# VTTX.net
KiCad netlist of a schematic drawn in Altium Designer
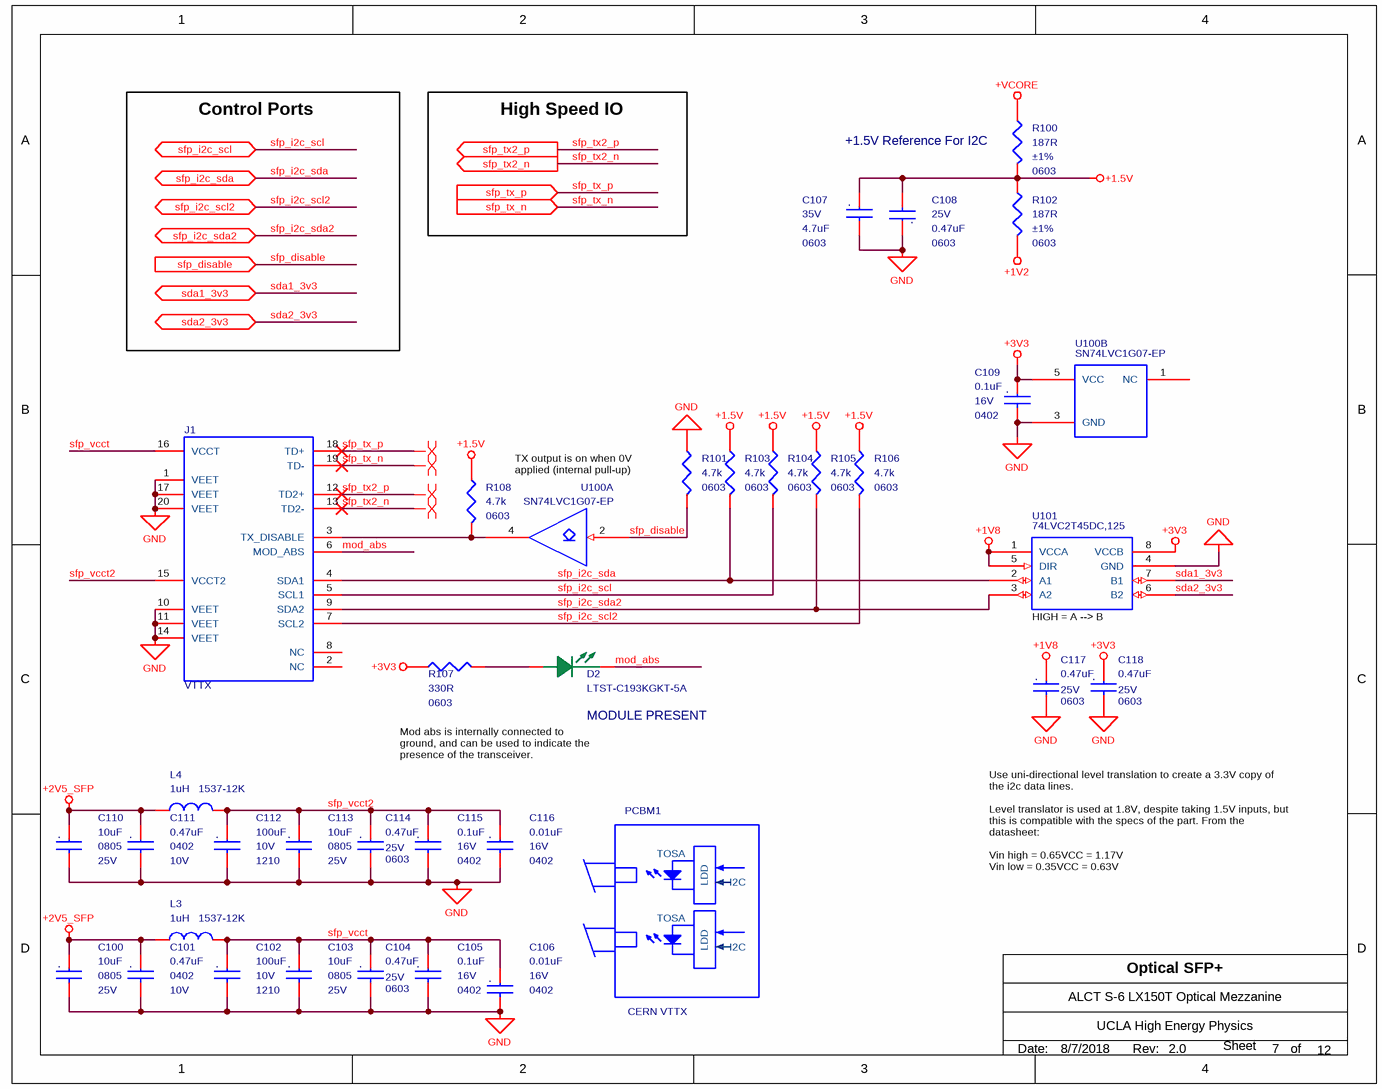
[diagram p0: VTTX.SchDoc]

(export (version "E")
  (design (tool "Eeschema 10.0.6"))
  (components
    (comp (ref "C100")
      (value "10uF")
      (footprint "MC_S6/SM/C_0805_IPC")
      (description "CAP CER 10UF 25V X5R 0805")
      (fields
        (field (name "MANUFACTURER") "Murata Electronics North America")
        (field (name "MANUFACTURER PART NUMBER") "GRM21BR61E106KA73L")
        (field (name "VOLTAGE - RATED") "25V")
        (field (name "PACKAGE") "0805")
      )
      (libsource (lib "ALCT_MEZ_SPARTAN6_Library") (part "GRM21BR61E106KA73L"))
    )
    (comp (ref "C101")
      (value "0.47uF")
      (footprint "MC_S6/SM/C_0402_IPC")
      (description "CAP CER 0.47UF 10V X5R 0402")
      (fields
        (field (name "MANUFACTURER") "Murata Electronics North America")
        (field (name "MANUFACTURER PART NUMBER") "GRM155R61A474KE15J")
        (field (name "VOLTAGE - RATED") "10V")
        (field (name "PACKAGE") "0402")
      )
      (libsource (lib "ALCT_MEZ_SPARTAN6_Library") (part "GRM155R61A474KE15J"))
    )
    (comp (ref "C102")
      (value "100uF")
      (footprint "MC_S6/SM/C_1210_IPC")
      (description "CAP CER 100UF 10V X5R 1210")
      (fields
        (field (name "MANUFACTURER") "Taiyo Yuden")
        (field (name "MANUFACTURER PART NUMBER") "LMK325BJ107MM-T")
        (field (name "VOLTAGE - RATED") "10V")
        (field (name "PACKAGE") "1210")
      )
      (libsource (lib "ALCT_MEZ_SPARTAN6_Library") (part "LMK325BJ107MM-T"))
    )
    (comp (ref "C103")
      (value "10uF")
      (footprint "MC_S6/SM/C_0805_IPC")
      (description "CAP CER 10UF 25V X5R 0805")
      (fields
        (field (name "MANUFACTURER") "Murata Electronics North America")
        (field (name "MANUFACTURER PART NUMBER") "GRM21BR61E106KA73L")
        (field (name "VOLTAGE - RATED") "25V")
        (field (name "PACKAGE") "0805")
      )
      (libsource (lib "ALCT_MEZ_SPARTAN6_Library") (part "GRM21BR61E106KA73L"))
    )
    (comp (ref "C104")
      (value "0.47uF")
      (footprint "MC_S6/SM/C_0603_IPC")
      (description "CAP CER 0.47UF 25V X7R 0603")
      (fields
        (field (name "MANUFACTURER") "Murata")
        (field (name "MANUFACTURER PART NUMBER") "GRM188R71E474KA12D")
        (field (name "VOLTAGE - RATED") "25V")
        (field (name "PACKAGE") "0603")
      )
      (libsource (lib "ALCT_MEZ_SPARTAN6_Library") (part "GRM188R71E474KA12D"))
    )
    (comp (ref "C105")
      (value "0.1uF")
      (footprint "MC_S6/SM/C_0402_IPC")
      (description "CAP CER 0.1UF 16V X7R 0402")
      (fields
        (field (name "MANUFACTURER") "KEMET")
        (field (name "MANUFACTURER PART NUMBER") "C0402C104K4RACTU")
        (field (name "PACKAGE") "0402")
        (field (name "VOLTAGE - RATED") "16V")
      )
      (libsource (lib "ALCT_MEZ_SPARTAN6_Library") (part "C0402C104K4RACTU"))
    )
    (comp (ref "C106")
      (value "0.01uF")
      (footprint "MC_S6/SM/C_0402_IPC")
      (description "CAP CER 10nF 16V X7R 0402")
      (fields
        (field (name "MANUFACTURER") "KEMET")
        (field (name "MANUFACTURER PART NUMBER") "C0402C103K4RACTU")
        (field (name "VOLTAGE - RATED") "16V")
        (field (name "PACKAGE") "0402")
      )
      (libsource (lib "ALCT_MEZ_SPARTAN6_Library") (part "C0402C103K4RACTU"))
    )
    (comp (ref "C107")
      (value "4.7uF")
      (footprint "MC_S6/SM/C_0603_IPC")
      (description "CAP CER 4.7UF 35V X5R 0603")
      (fields
        (field (name "MANUFACTURER") "Murata")
        (field (name "MANUFACTURER PART NUMBER") "GRM188R6YA475KE15D")
        (field (name "VOLTAGE - RATED") "35V")
        (field (name "PACKAGE") "0603")
      )
      (libsource (lib "ALCT_MEZ_SPARTAN6_Library") (part "GRM188R6YA475KE15D"))
    )
    (comp (ref "C108")
      (value "0.47uF")
      (footprint "MC_S6/SM/C_0603_IPC")
      (description "CAP CER 0.47UF 25V X7R 0603")
      (fields
        (field (name "MANUFACTURER") "Murata")
        (field (name "MANUFACTURER PART NUMBER") "GRM188R71E474KA12D")
        (field (name "VOLTAGE - RATED") "25V")
        (field (name "PACKAGE") "0603")
      )
      (libsource (lib "ALCT_MEZ_SPARTAN6_Library") (part "GRM188R71E474KA12D"))
    )
    (comp (ref "C109")
      (value "0.1uF")
      (footprint "MC_S6/SM/C_0402_IPC")
      (description "CAP CER 0.1UF 16V X7R 0402")
      (fields
        (field (name "MANUFACTURER") "KEMET")
        (field (name "MANUFACTURER PART NUMBER") "C0402C104K4RACTU")
        (field (name "PACKAGE") "0402")
        (field (name "VOLTAGE - RATED") "16V")
      )
      (libsource (lib "ALCT_MEZ_SPARTAN6_Library") (part "C0402C104K4RACTU"))
    )
    (comp (ref "C110")
      (value "10uF")
      (footprint "MC_S6/SM/C_0805_IPC")
      (description "CAP CER 10UF 25V X5R 0805")
      (fields
        (field (name "MANUFACTURER") "Murata Electronics North America")
        (field (name "MANUFACTURER PART NUMBER") "GRM21BR61E106KA73L")
        (field (name "VOLTAGE - RATED") "25V")
        (field (name "PACKAGE") "0805")
      )
      (libsource (lib "ALCT_MEZ_SPARTAN6_Library") (part "GRM21BR61E106KA73L"))
    )
    (comp (ref "C111")
      (value "0.47uF")
      (footprint "MC_S6/SM/C_0402_IPC")
      (description "CAP CER 0.47UF 10V X5R 0402")
      (fields
        (field (name "MANUFACTURER") "Murata Electronics North America")
        (field (name "MANUFACTURER PART NUMBER") "GRM155R61A474KE15J")
        (field (name "VOLTAGE - RATED") "10V")
        (field (name "PACKAGE") "0402")
      )
      (libsource (lib "ALCT_MEZ_SPARTAN6_Library") (part "GRM155R61A474KE15J"))
    )
    (comp (ref "C112")
      (value "100uF")
      (footprint "MC_S6/SM/C_1210_IPC")
      (description "CAP CER 100UF 10V X5R 1210")
      (fields
        (field (name "MANUFACTURER") "Taiyo Yuden")
        (field (name "MANUFACTURER PART NUMBER") "LMK325BJ107MM-T")
        (field (name "VOLTAGE - RATED") "10V")
        (field (name "PACKAGE") "1210")
      )
      (libsource (lib "ALCT_MEZ_SPARTAN6_Library") (part "LMK325BJ107MM-T"))
    )
    (comp (ref "C113")
      (value "10uF")
      (footprint "MC_S6/SM/C_0805_IPC")
      (description "CAP CER 10UF 25V X5R 0805")
      (fields
        (field (name "MANUFACTURER") "Murata Electronics North America")
        (field (name "MANUFACTURER PART NUMBER") "GRM21BR61E106KA73L")
        (field (name "VOLTAGE - RATED") "25V")
        (field (name "PACKAGE") "0805")
      )
      (libsource (lib "ALCT_MEZ_SPARTAN6_Library") (part "GRM21BR61E106KA73L"))
    )
    (comp (ref "C114")
      (value "0.47uF")
      (footprint "MC_S6/SM/C_0603_IPC")
      (description "CAP CER 0.47UF 25V X7R 0603")
      (fields
        (field (name "MANUFACTURER") "Murata")
        (field (name "MANUFACTURER PART NUMBER") "GRM188R71E474KA12D")
        (field (name "VOLTAGE - RATED") "25V")
        (field (name "PACKAGE") "0603")
      )
      (libsource (lib "ALCT_MEZ_SPARTAN6_Library") (part "GRM188R71E474KA12D"))
    )
    (comp (ref "C115")
      (value "0.1uF")
      (footprint "MC_S6/SM/C_0402_IPC")
      (description "CAP CER 0.1UF 16V X7R 0402")
      (fields
        (field (name "MANUFACTURER") "KEMET")
        (field (name "MANUFACTURER PART NUMBER") "C0402C104K4RACTU")
        (field (name "PACKAGE") "0402")
        (field (name "VOLTAGE - RATED") "16V")
      )
      (libsource (lib "ALCT_MEZ_SPARTAN6_Library") (part "C0402C104K4RACTU"))
    )
    (comp (ref "C116")
      (value "0.01uF")
      (footprint "MC_S6/SM/C_0402_IPC")
      (description "CAP CER 10nF 16V X7R 0402")
      (fields
        (field (name "MANUFACTURER") "KEMET")
        (field (name "MANUFACTURER PART NUMBER") "C0402C103K4RACTU")
        (field (name "VOLTAGE - RATED") "16V")
        (field (name "PACKAGE") "0402")
      )
      (libsource (lib "ALCT_MEZ_SPARTAN6_Library") (part "C0402C103K4RACTU"))
    )
    (comp (ref "C117")
      (value "0.47uF")
      (footprint "MC_S6/SM/C_0603_IPC")
      (description "CAP CER 0.47UF 25V X7R 0603")
      (fields
        (field (name "MANUFACTURER") "Murata")
        (field (name "MANUFACTURER PART NUMBER") "GRM188R71E474KA12D")
        (field (name "VOLTAGE - RATED") "25V")
        (field (name "PACKAGE") "0603")
      )
      (libsource (lib "ALCT_MEZ_SPARTAN6_Library") (part "GRM188R71E474KA12D"))
    )
    (comp (ref "C118")
      (value "0.47uF")
      (footprint "MC_S6/SM/C_0603_IPC")
      (description "CAP CER 0.47UF 25V X7R 0603")
      (fields
        (field (name "MANUFACTURER") "Murata")
        (field (name "MANUFACTURER PART NUMBER") "GRM188R71E474KA12D")
        (field (name "VOLTAGE - RATED") "25V")
        (field (name "PACKAGE") "0603")
      )
      (libsource (lib "ALCT_MEZ_SPARTAN6_Library") (part "GRM188R71E474KA12D"))
    )
    (comp (ref "D2")
      (value "LTST-C193KGKT-5A")
      (footprint "MC_S6/SM/LED_0603")
      (description "LED GREEN CLEAR 0603 SMD")
      (fields (field (name "MANUFACTURER") "Lite-On Inc."))
      (libsource (lib "ALCT_MEZ_SPARTAN6_Library") (part "LTST-C193KGKT-5A"))
    )
    (comp (ref "J1")
      (value "VTTX")
      (footprint "MC_S6/SM/TE-1888247-1")
      (description "CONN FP+ CAGE 30AU SMD")
      (fields
        (field (name "MANUFACTURER") "TE Connectivity AMP Connectors")
        (field (name "MANUFACTURER PART NUMBER") "1888247-1")
      )
      (libsource (lib "ALCT_MEZ_SPARTAN6_Library") (part "VTTX"))
    )
    (comp (ref "L3")
      (value "1uH")
      (footprint "MC_S6/TH/DELEVAN1537")
      (description "IND, Air Core, 1uH, 880mA, TH")
      (fields
        (field (name "MFGR_ID") "1537-12K")
        (field (name "MANUFACTURER") "API Delevan Inc.")
        (field (name "MANUFACTURER PART NUMBER") "1537-12K")
      )
      (libsource (lib "ALCT_MEZ_SPARTAN6_Library") (part "1537-12K"))
    )
    (comp (ref "L4")
      (value "1uH")
      (footprint "MC_S6/TH/DELEVAN1537")
      (description "IND, Air Core, 1uH, 880mA, TH")
      (fields
        (field (name "MFGR_ID") "1537-12K")
        (field (name "MANUFACTURER") "API Delevan Inc.")
        (field (name "MANUFACTURER PART NUMBER") "1537-12K")
      )
      (libsource (lib "ALCT_MEZ_SPARTAN6_Library") (part "1537-12K"))
    )
    (comp (ref "PCBM1")
      (value "CERN VTTX")
      (footprint "PCBM_CERN_VTTX V2.1")
      (description "Versatile Twin Transmitter Module")
      (fields
        (field (name "PART NUMBER") "PCBM_CERN_VTTX V2.1_a")
        (field (name "MANUFACTURER") "CERN")
        (field (name "AUTHOR") "CERN DEM JLC")
      )
      (libsource (lib "VTRX-VTTX") (part "PCBM_CERN_VTTX V2.1_a"))
    )
    (comp (ref "R100")
      (value "187R")
      (footprint "MC_S6/SM/R_0603_IPC")
      (description "RES SMD 187 OHM 1% 1/10W 0603")
      (fields
        (field (name "MANUFACTURER") "Panasonic Electronic Components")
        (field (name "MANUFACTURER PART NUMBER") "ERJ-3EKF1870V")
        (field (name "TOLERANCE") "±1%")
        (field (name "SUPPLIER DEVICE PACKAGE") "0603")
      )
      (libsource (lib "ALCT_MEZ_SPARTAN6_Library") (part "ERJ-3EKF1870V"))
    )
    (comp (ref "R101")
      (value "4.7k")
      (footprint "MC_S6/SM/R_0603_IPC")
      (description "RES SMD 4.7K OHM 1% 1/10W 0603")
      (fields
        (field (name "MANUFACTURER") "Bourns Inc.")
        (field (name "MANUFACTURER PART NUMBER") "CR0603-FX-4701ELF")
        (field (name "SUPPLIER DEVICE PACKAGE") "0603")
      )
      (libsource (lib "ALCT_MEZ_SPARTAN6_Library") (part "CR0603-FX-4701ELF"))
    )
    (comp (ref "R102")
      (value "187R")
      (footprint "MC_S6/SM/R_0603_IPC")
      (description "RES SMD 187 OHM 1% 1/10W 0603")
      (fields
        (field (name "MANUFACTURER") "Panasonic Electronic Components")
        (field (name "MANUFACTURER PART NUMBER") "ERJ-3EKF1870V")
        (field (name "TOLERANCE") "±1%")
        (field (name "SUPPLIER DEVICE PACKAGE") "0603")
      )
      (libsource (lib "ALCT_MEZ_SPARTAN6_Library") (part "ERJ-3EKF1870V"))
    )
    (comp (ref "R103")
      (value "4.7k")
      (footprint "MC_S6/SM/R_0603_IPC")
      (description "RES SMD 4.7K OHM 1% 1/10W 0603")
      (fields
        (field (name "TOLERANCE") "±1%")
        (field (name "MANUFACTURER") "Bourns Inc.")
        (field (name "SUPPLIER DEVICE PACKAGE") "0603")
      )
      (libsource (lib "ALCT_MEZ_SPARTAN6_Library") (part "CR0603-FX-4701ELF"))
    )
    (comp (ref "R104")
      (value "4.7k")
      (footprint "MC_S6/SM/R_0603_IPC")
      (description "RES SMD 4.7K OHM 1% 1/10W 0603")
      (fields
        (field (name "TOLERANCE") "±1%")
        (field (name "MANUFACTURER") "Bourns Inc.")
        (field (name "SUPPLIER DEVICE PACKAGE") "0603")
      )
      (libsource (lib "ALCT_MEZ_SPARTAN6_Library") (part "CR0603-FX-4701ELF"))
    )
    (comp (ref "R105")
      (value "4.7k")
      (footprint "MC_S6/SM/R_0603_IPC")
      (description "RES SMD 4.7K OHM 1% 1/10W 0603")
      (fields
        (field (name "TOLERANCE") "±1%")
        (field (name "MANUFACTURER") "Bourns Inc.")
        (field (name "SUPPLIER DEVICE PACKAGE") "0603")
      )
      (libsource (lib "ALCT_MEZ_SPARTAN6_Library") (part "CR0603-FX-4701ELF"))
    )
    (comp (ref "R106")
      (value "4.7k")
      (footprint "MC_S6/SM/R_0603_IPC")
      (description "RES SMD 4.7K OHM 1% 1/10W 0603")
      (fields
        (field (name "TOLERANCE") "±1%")
        (field (name "MANUFACTURER") "Bourns Inc.")
        (field (name "SUPPLIER DEVICE PACKAGE") "0603")
      )
      (libsource (lib "ALCT_MEZ_SPARTAN6_Library") (part "CR0603-FX-4701ELF"))
    )
    (comp (ref "R107")
      (value "330R")
      (footprint "MC_S6/SM/R_0603_IPC")
      (description "RES SMD 330 OHM 1% 1/10W 0603")
      (fields
        (field (name "TOLERANCE") "±1%")
        (field (name "MANUFACTURER") "Bourns Inc.")
        (field (name "SUPPLIER DEVICE PACKAGE") "0603")
      )
      (libsource (lib "ALCT_MEZ_SPARTAN6_Library") (part "CR0603-FX-3300ELF"))
    )
    (comp (ref "R108")
      (value "4.7k")
      (footprint "MC_S6/SM/R_0603_IPC")
      (description "RES SMD 4.7K OHM 1% 1/10W 0603")
      (fields
        (field (name "TOLERANCE") "±1%")
        (field (name "MANUFACTURER") "Bourns Inc.")
        (field (name "SUPPLIER DEVICE PACKAGE") "0603")
      )
      (libsource (lib "ALCT_MEZ_SPARTAN6_Library") (part "CR0603-FX-4701ELF"))
    )
    (comp (ref "U100")
      (value "SN74LVC1G07-EP")
      (footprint "MC_S6/SM/SOT_SC70_DCK5")
      (description "IC BUFF/DVR NON-INVERT Open Drain SC70-5")
      (fields
        (field (name "MANUFACTURER") "Texas Instruments")
        (field (name "MANUFACTURER PART NUMBER") "SN74LVC1G07MDCKREP")
      )
      (libsource (lib "ALCT_MEZ_SPARTAN6_Library") (part "SN74LVC1G07-EP"))
    )
    (comp (ref "U101")
      (value "74LVC2T45DC,125")
      (footprint "VSSOP8 SOT765-1")
      (description "IC TRNSLTR BIDIRECTIONAL 8VSSOP")
      (fields (field (name "MANUFACTURER") "Nexperia USA Inc.") (field (name "BASE PART NUMBER") "74LVC2T45"))
      (libsource (lib "ALCT_MEZ_SPARTAN6_Library") (part "74LVC2T45DC,125"))
    )
  )
  (nets
    (net (code "1") (name "+1.5V") (class "Default")
      (node (ref "C107") (pin "1") (pinfunction "1_1") (pintype "passive"))
      (node (ref "C108") (pin "2") (pinfunction "2_2") (pintype "passive"))
      (node (ref "R100") (pin "2") (pinfunction "2_2") (pintype "passive"))
      (node (ref "R102") (pin "1") (pinfunction "1_1") (pintype "passive"))
      (node (ref "R103") (pin "1") (pinfunction "1_1") (pintype "passive"))
      (node (ref "R104") (pin "1") (pinfunction "1_1") (pintype "passive"))
      (node (ref "R105") (pin "1") (pinfunction "1_1") (pintype "passive"))
      (node (ref "R106") (pin "1") (pinfunction "1_1") (pintype "passive"))
      (node (ref "R108") (pin "1") (pinfunction "1_1") (pintype "passive"))
    )
    (net (code "2") (name "+1V2") (class "Default")
      (node (ref "R102") (pin "2") (pinfunction "2_2") (pintype "passive"))
    )
    (net (code "3") (name "+1V8") (class "Default")
      (node (ref "C117") (pin "1") (pinfunction "1_1") (pintype "passive"))
      (node (ref "U101") (pin "1") (pinfunction "VCCA_1") (pintype "power_in"))
      (node (ref "U101") (pin "5") (pinfunction "DIR_5") (pintype "input"))
    )
    (net (code "4") (name "+2V5_SFP") (class "Default")
      (node (ref "C100") (pin "1") (pinfunction "1_1") (pintype "passive"))
      (node (ref "C101") (pin "1") (pinfunction "1_1") (pintype "passive"))
      (node (ref "C110") (pin "1") (pinfunction "1_1") (pintype "passive"))
      (node (ref "C111") (pin "1") (pinfunction "1_1") (pintype "passive"))
      (node (ref "L3") (pin "2") (pinfunction "2_2") (pintype "passive"))
      (node (ref "L4") (pin "2") (pinfunction "2_2") (pintype "passive"))
    )
    (net (code "5") (name "+3V3") (class "Default")
      (node (ref "C109") (pin "1") (pinfunction "1_1") (pintype "passive"))
      (node (ref "C118") (pin "1") (pinfunction "1_1") (pintype "passive"))
      (node (ref "R107") (pin "1") (pinfunction "1_1") (pintype "passive"))
      (node (ref "U100") (pin "5") (pinfunction "VCC_5") (pintype "power_in"))
      (node (ref "U101") (pin "8") (pinfunction "VCCB_8") (pintype "passive"))
    )
    (net (code "6") (name "+VCORE") (class "Default")
      (node (ref "R100") (pin "1") (pinfunction "1_1") (pintype "passive"))
    )
    (net (code "7") (name "/mod_abs") (class "Default")
      (node (ref "D2") (pin "K") (pinfunction "CATHODE_K") (pintype "passive"))
      (node (ref "J1") (pin "6") (pinfunction "MOD_ABS_6") (pintype "passive"))
    )
    (net (code "8") (name "/sda1_3v3") (class "Default")
      (node (ref "U101") (pin "7") (pinfunction "B1_7") (pintype "bidirectional"))
    )
    (net (code "9") (name "/sda2_3v3") (class "Default")
      (node (ref "U101") (pin "6") (pinfunction "B2_6") (pintype "bidirectional"))
    )
    (net (code "10") (name "/sfp_disable") (class "Default")
      (node (ref "R101") (pin "2") (pinfunction "2_2") (pintype "passive"))
      (node (ref "U100") (pin "2") (pinfunction "A_2") (pintype "input"))
    )
    (net (code "11") (name "/sfp_i2c_scl") (class "Default")
      (node (ref "J1") (pin "5") (pinfunction "SCL1_5") (pintype "passive"))
      (node (ref "R104") (pin "2") (pinfunction "2_2") (pintype "passive"))
    )
    (net (code "12") (name "/sfp_i2c_scl2") (class "Default")
      (node (ref "J1") (pin "7") (pinfunction "SCL2_7") (pintype "passive"))
      (node (ref "R106") (pin "2") (pinfunction "2_2") (pintype "passive"))
    )
    (net (code "13") (name "/sfp_i2c_sda") (class "Default")
      (node (ref "J1") (pin "4") (pinfunction "SDA1_4") (pintype "passive"))
      (node (ref "R103") (pin "2") (pinfunction "2_2") (pintype "passive"))
      (node (ref "U101") (pin "2") (pinfunction "A1_2") (pintype "bidirectional"))
    )
    (net (code "14") (name "/sfp_i2c_sda2") (class "Default")
      (node (ref "J1") (pin "9") (pinfunction "SDA2_9") (pintype "passive"))
      (node (ref "R105") (pin "2") (pinfunction "2_2") (pintype "passive"))
      (node (ref "U101") (pin "3") (pinfunction "A2_3") (pintype "bidirectional"))
    )
    (net (code "15") (name "/sfp_tx2_n") (class "Default")
      (node (ref "J1") (pin "13") (pinfunction "TD2-_13") (pintype "passive"))
    )
    (net (code "16") (name "/sfp_tx2_p") (class "Default")
      (node (ref "J1") (pin "12") (pinfunction "TD2+_12") (pintype "passive"))
    )
    (net (code "17") (name "/sfp_tx_n") (class "Default")
      (node (ref "J1") (pin "19") (pinfunction "TD-_19") (pintype "passive"))
    )
    (net (code "18") (name "/sfp_tx_p") (class "Default")
      (node (ref "J1") (pin "18") (pinfunction "TD+_18") (pintype "passive"))
    )
    (net (code "19") (name "/sfp_vcct") (class "Default")
      (node (ref "C102") (pin "1") (pinfunction "1_1") (pintype "passive"))
      (node (ref "C103") (pin "1") (pinfunction "1_1") (pintype "passive"))
      (node (ref "C104") (pin "1") (pinfunction "1_1") (pintype "passive"))
      (node (ref "C105") (pin "1") (pinfunction "1_1") (pintype "passive"))
      (node (ref "C106") (pin "1") (pinfunction "1_1") (pintype "passive"))
      (node (ref "J1") (pin "16") (pinfunction "VCCT_16") (pintype "passive"))
      (node (ref "L3") (pin "1") (pinfunction "1_1") (pintype "passive"))
    )
    (net (code "20") (name "/sfp_vcct2") (class "Default")
      (node (ref "C112") (pin "1") (pinfunction "1_1") (pintype "passive"))
      (node (ref "C113") (pin "1") (pinfunction "1_1") (pintype "passive"))
      (node (ref "C114") (pin "1") (pinfunction "1_1") (pintype "passive"))
      (node (ref "C115") (pin "1") (pinfunction "1_1") (pintype "passive"))
      (node (ref "C116") (pin "1") (pinfunction "1_1") (pintype "passive"))
      (node (ref "J1") (pin "15") (pinfunction "VCCT2_15") (pintype "passive"))
      (node (ref "L4") (pin "1") (pinfunction "1_1") (pintype "passive"))
    )
    (net (code "21") (name "GND") (class "Default")
      (node (ref "C100") (pin "2") (pinfunction "2_2") (pintype "passive"))
      (node (ref "C101") (pin "2") (pinfunction "2_2") (pintype "passive"))
      (node (ref "C102") (pin "2") (pinfunction "2_2") (pintype "passive"))
      (node (ref "C103") (pin "2") (pinfunction "2_2") (pintype "passive"))
      (node (ref "C104") (pin "2") (pinfunction "2_2") (pintype "passive"))
      (node (ref "C105") (pin "2") (pinfunction "2_2") (pintype "passive"))
      (node (ref "C106") (pin "2") (pinfunction "2_2") (pintype "passive"))
      (node (ref "C107") (pin "2") (pinfunction "2_2") (pintype "passive"))
      (node (ref "C108") (pin "1") (pinfunction "1_1") (pintype "passive"))
      (node (ref "C109") (pin "2") (pinfunction "2_2") (pintype "passive"))
      (node (ref "C110") (pin "2") (pinfunction "2_2") (pintype "passive"))
      (node (ref "C111") (pin "2") (pinfunction "2_2") (pintype "passive"))
      (node (ref "C112") (pin "2") (pinfunction "2_2") (pintype "passive"))
      (node (ref "C113") (pin "2") (pinfunction "2_2") (pintype "passive"))
      (node (ref "C114") (pin "2") (pinfunction "2_2") (pintype "passive"))
      (node (ref "C115") (pin "2") (pinfunction "2_2") (pintype "passive"))
      (node (ref "C116") (pin "2") (pinfunction "2_2") (pintype "passive"))
      (node (ref "C117") (pin "2") (pinfunction "2_2") (pintype "passive"))
      (node (ref "C118") (pin "2") (pinfunction "2_2") (pintype "passive"))
      (node (ref "J1") (pin "1") (pinfunction "VEET_1") (pintype "passive"))
      (node (ref "J1") (pin "10") (pinfunction "VEET_10") (pintype "passive"))
      (node (ref "J1") (pin "11") (pinfunction "VEET_11") (pintype "passive"))
      (node (ref "J1") (pin "14") (pinfunction "VEET_14") (pintype "passive"))
      (node (ref "J1") (pin "17") (pinfunction "VEET_17") (pintype "passive"))
      (node (ref "J1") (pin "20") (pinfunction "VEET_20") (pintype "passive"))
      (node (ref "R101") (pin "1") (pinfunction "1_1") (pintype "passive"))
      (node (ref "U100") (pin "3") (pinfunction "GND_3") (pintype "power_in"))
      (node (ref "U101") (pin "4") (pinfunction "GND_4") (pintype "power_in"))
    )
    (net (code "22") (name "Net-(D2-ANODE)") (class "Default")
      (node (ref "D2") (pin "A") (pinfunction "ANODE_A") (pintype "passive"))
      (node (ref "R107") (pin "2") (pinfunction "2_2") (pintype "passive"))
    )
    (net (code "23") (name "Net-(J1-TX_DISABLE)") (class "Default")
      (node (ref "J1") (pin "3") (pinfunction "TX_DISABLE_3") (pintype "passive"))
      (node (ref "R108") (pin "2") (pinfunction "2_2") (pintype "passive"))
      (node (ref "U100") (pin "4") (pinfunction "Y_4") (pintype "open_collector"))
    )
    (net (code "24") (name "unconnected-(J1-NC-Pad2)") (class "Default")
      (node (ref "J1") (pin "2") (pinfunction "NC_2") (pintype "passive"))
    )
    (net (code "25") (name "unconnected-(J1-NC-Pad8)") (class "Default")
      (node (ref "J1") (pin "8") (pinfunction "NC_8") (pintype "passive"))
    )
    (net (code "26") (name "unconnected-(U100B-NC-Pad1)") (class "Default")
      (node (ref "U100") (pin "1") (pinfunction "NC_1") (pintype "passive"))
    )
  )
)
